# LED_Controller_4Channels.net
KiCad netlist of a schematic drawn in Altium Designer
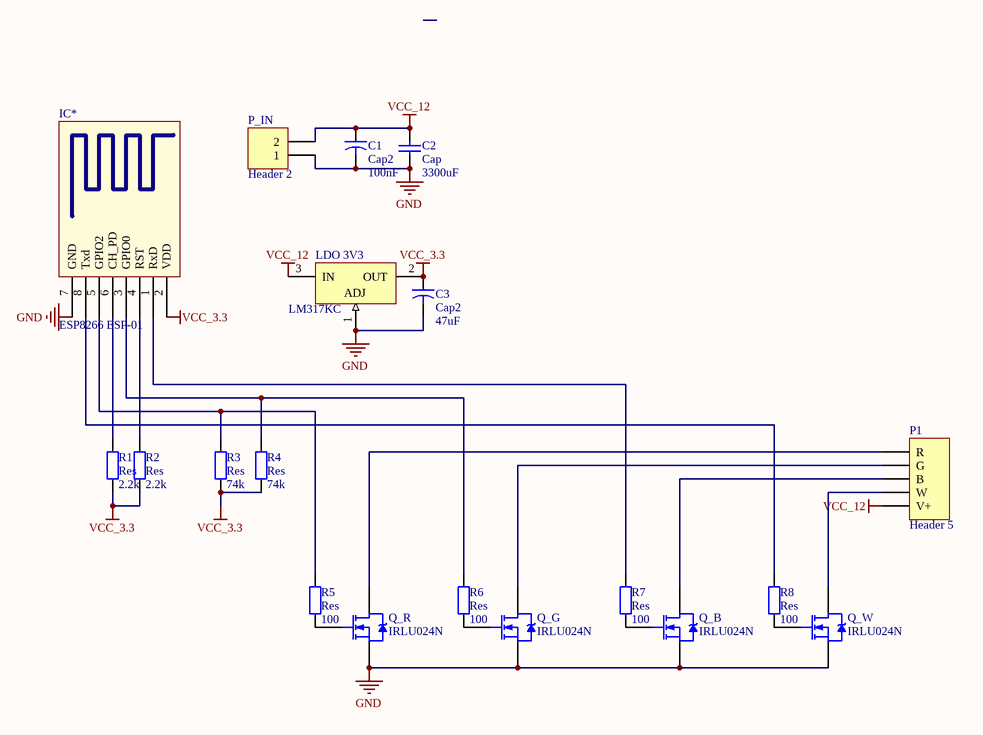
[diagram p0: LED_Controller_4Channels.SchDoc]

(export (version "E")
  (design (tool "Eeschema 10.0.6"))
  (components
    (comp (ref "C1")
      (value "Cap2")
      (footprint "CAPR5-4X5")
      (description "Capacitor")
      (fields (field (name "ALTIUM_VALUE") "100nF") (field (name "PUBLISHER") "Altium Limited"))
      (libsource (lib "Miscellaneous Devices") (part "Cap2"))
    )
    (comp (ref "C2")
      (value "Cap")
      (footprint "RAD-0.3")
      (description "Capacitor")
      (fields (field (name "ALTIUM_VALUE") "3300uF") (field (name "PUBLISHER") "Altium Limited"))
      (libsource (lib "Miscellaneous Devices") (part "Cap"))
    )
    (comp (ref "C3")
      (value "Cap2")
      (footprint "CAPR5-4X5")
      (description "Capacitor")
      (fields (field (name "ALTIUM_VALUE") "47uF") (field (name "PUBLISHER") "Altium Limited"))
      (libsource (lib "Miscellaneous Devices") (part "Cap2"))
    )
    (comp (ref "IC*")
      (value "ESP8266 ESP-01")
      (footprint "ESP8266:ESP8266 ESP-01")
      (libsource (lib "ESP8266") (part "ESP8266 ESP-01"))
    )
    (comp (ref "LDO 3V3")
      (value "LM317KC")
      (footprint "KC03")
      (description "3-Terminal Adjustable Regulator")
      (fields (field (name "PUBLISHER") "Altium Limited"))
      (libsource (lib "TI Power Mgt Voltage Regulator") (part "LM317KC"))
    )
    (comp (ref "P1")
      (value "Header 5")
      (footprint "HDR1X5")
      (description "Header, 5-Pin")
      (fields (field (name "PUBLISHER") "Altium Limited"))
      (libsource (lib "Miscellaneous Connectors") (part "Header 5"))
    )
    (comp (ref "P_IN")
      (value "Header 2")
      (footprint "HDR1X2")
      (description "Header, 2-Pin")
      (fields (field (name "PUBLISHER") "Altium Limited"))
      (libsource (lib "Miscellaneous Connectors") (part "Header 2"))
    )
    (comp (ref "Q_B")
      (value "IRLU024N")
      (footprint "D-Pack")
      (description "HEXFET Power MOSFET")
      (fields (field (name "PUBLISHER") "Altium Limited"))
      (libsource (lib "cadLib") (part "IRLU024N"))
    )
    (comp (ref "Q_G")
      (value "IRLU024N")
      (footprint "D-Pack")
      (description "HEXFET Power MOSFET")
      (fields (field (name "PUBLISHER") "Altium Limited"))
      (libsource (lib "cadLib") (part "IRLU024N"))
    )
    (comp (ref "Q_R")
      (value "IRLU024N")
      (footprint "D-Pack")
      (description "HEXFET Power MOSFET")
      (fields (field (name "PUBLISHER") "Altium Limited"))
      (libsource (lib "cadLib") (part "IRLU024N"))
    )
    (comp (ref "Q_W")
      (value "IRLU024N")
      (footprint "D-Pack")
      (description "HEXFET Power MOSFET")
      (fields (field (name "PUBLISHER") "Altium Limited"))
      (libsource (lib "cadLib") (part "IRLU024N"))
    )
    (comp (ref "R1")
      (value "Res")
      (footprint "0805")
      (description "Resistor")
      (fields (field (name "ALTIUM_VALUE") "2.2k") (field (name "PUBLISHER") "Altium Limited"))
      (libsource (lib "") (part "Res_1"))
    )
    (comp (ref "R2")
      (value "Res")
      (footprint "0805")
      (description "Resistor")
      (fields (field (name "ALTIUM_VALUE") "2.2k") (field (name "PUBLISHER") "Altium Limited"))
      (libsource (lib "") (part "Res_1"))
    )
    (comp (ref "R3")
      (value "Res")
      (footprint "0805")
      (description "Resistor")
      (fields (field (name "ALTIUM_VALUE") "74k") (field (name "PUBLISHER") "Altium Limited"))
      (libsource (lib "MiscDevices") (part "Res"))
    )
    (comp (ref "R4")
      (value "Res")
      (footprint "0805")
      (description "Resistor")
      (fields (field (name "ALTIUM_VALUE") "74k") (field (name "PUBLISHER") "Altium Limited"))
      (libsource (lib "MiscDevices") (part "Res"))
    )
    (comp (ref "R5")
      (value "Res")
      (footprint "0805")
      (description "Resistor")
      (fields (field (name "ALTIUM_VALUE") "100") (field (name "PUBLISHER") "Altium Limited"))
      (libsource (lib "") (part "Res_1"))
    )
    (comp (ref "R6")
      (value "Res")
      (footprint "0805")
      (description "Resistor")
      (fields (field (name "ALTIUM_VALUE") "100") (field (name "PUBLISHER") "Altium Limited"))
      (libsource (lib "") (part "Res_1"))
    )
    (comp (ref "R7")
      (value "Res")
      (footprint "0805")
      (description "Resistor")
      (fields (field (name "ALTIUM_VALUE") "100") (field (name "PUBLISHER") "Altium Limited"))
      (libsource (lib "") (part "Res_1"))
    )
    (comp (ref "R8")
      (value "Res")
      (footprint "0805")
      (description "Resistor")
      (fields (field (name "ALTIUM_VALUE") "100") (field (name "PUBLISHER") "Altium Limited"))
      (libsource (lib "") (part "Res_1"))
    )
  )
  (nets
    (net (code "1") (name "GND") (class "Default")
      (node (ref "C1") (pin "2") (pinfunction "2_2") (pintype "passive"))
      (node (ref "C2") (pin "1") (pinfunction "1_1") (pintype "passive"))
      (node (ref "C3") (pin "2") (pinfunction "2_2") (pintype "passive"))
      (node (ref "IC*") (pin "7") (pinfunction "GND_7") (pintype "passive"))
      (node (ref "LDO 3V3") (pin "1") (pinfunction "ADJ_1") (pintype "input"))
      (node (ref "P_IN") (pin "1") (pinfunction "1_1") (pintype "passive"))
      (node (ref "Q_B") (pin "3") (pinfunction "S_3") (pintype "passive"))
      (node (ref "Q_G") (pin "3") (pinfunction "S_3") (pintype "passive"))
      (node (ref "Q_R") (pin "3") (pinfunction "S_3") (pintype "passive"))
      (node (ref "Q_W") (pin "3") (pinfunction "S_3") (pintype "passive"))
    )
    (net (code "2") (name "Net-(IC*-CH_PD)") (class "Default")
      (node (ref "IC*") (pin "6") (pinfunction "CH_PD_6") (pintype "passive"))
      (node (ref "R1") (pin "2") (pinfunction "2_2") (pintype "passive"))
    )
    (net (code "3") (name "Net-(IC*-GPIO0)") (class "Default")
      (node (ref "IC*") (pin "3") (pinfunction "GPIO0_3") (pintype "passive"))
      (node (ref "R4") (pin "1") (pinfunction "1_1") (pintype "passive"))
      (node (ref "R6") (pin "2") (pinfunction "2_2") (pintype "passive"))
    )
    (net (code "4") (name "Net-(IC*-GPIO2)") (class "Default")
      (node (ref "IC*") (pin "5") (pinfunction "GPIO2_5") (pintype "passive"))
      (node (ref "R3") (pin "1") (pinfunction "1_1") (pintype "passive"))
      (node (ref "R5") (pin "2") (pinfunction "2_2") (pintype "passive"))
    )
    (net (code "5") (name "Net-(IC*-RST)") (class "Default")
      (node (ref "IC*") (pin "4") (pinfunction "RST_4") (pintype "passive"))
      (node (ref "R2") (pin "2") (pinfunction "2_2") (pintype "passive"))
    )
    (net (code "6") (name "Net-(IC*-RxD)") (class "Default")
      (node (ref "IC*") (pin "1") (pinfunction "RxD_1") (pintype "passive"))
      (node (ref "R7") (pin "2") (pinfunction "2_2") (pintype "passive"))
    )
    (net (code "7") (name "Net-(IC*-Txd)") (class "Default")
      (node (ref "IC*") (pin "8") (pinfunction "Txd_8") (pintype "passive"))
      (node (ref "R8") (pin "2") (pinfunction "2_2") (pintype "passive"))
    )
    (net (code "8") (name "Net-(P1-B)") (class "Default")
      (node (ref "P1") (pin "3") (pinfunction "B_3") (pintype "passive"))
      (node (ref "Q_B") (pin "2") (pinfunction "D_2") (pintype "passive"))
    )
    (net (code "9") (name "Net-(P1-G)") (class "Default")
      (node (ref "P1") (pin "2") (pinfunction "G_2") (pintype "passive"))
      (node (ref "Q_G") (pin "2") (pinfunction "D_2") (pintype "passive"))
    )
    (net (code "10") (name "Net-(P1-R)") (class "Default")
      (node (ref "P1") (pin "1") (pinfunction "R_1") (pintype "passive"))
      (node (ref "Q_R") (pin "2") (pinfunction "D_2") (pintype "passive"))
    )
    (net (code "11") (name "Net-(P1-W)") (class "Default")
      (node (ref "P1") (pin "4") (pinfunction "W_4") (pintype "passive"))
      (node (ref "Q_W") (pin "2") (pinfunction "D_2") (pintype "passive"))
    )
    (net (code "12") (name "Net-(Q_B-G)") (class "Default")
      (node (ref "Q_B") (pin "1") (pinfunction "G_1") (pintype "passive"))
      (node (ref "R7") (pin "1") (pinfunction "1_1") (pintype "passive"))
    )
    (net (code "13") (name "Net-(Q_G-G)") (class "Default")
      (node (ref "Q_G") (pin "1") (pinfunction "G_1") (pintype "passive"))
      (node (ref "R6") (pin "1") (pinfunction "1_1") (pintype "passive"))
    )
    (net (code "14") (name "Net-(Q_R-G)") (class "Default")
      (node (ref "Q_R") (pin "1") (pinfunction "G_1") (pintype "passive"))
      (node (ref "R5") (pin "1") (pinfunction "1_1") (pintype "passive"))
    )
    (net (code "15") (name "Net-(Q_W-G)") (class "Default")
      (node (ref "Q_W") (pin "1") (pinfunction "G_1") (pintype "passive"))
      (node (ref "R8") (pin "1") (pinfunction "1_1") (pintype "passive"))
    )
    (net (code "16") (name "VCC_3.3") (class "Default")
      (node (ref "C3") (pin "1") (pinfunction "1_1") (pintype "passive"))
      (node (ref "IC*") (pin "2") (pinfunction "VDD_2") (pintype "passive"))
      (node (ref "LDO 3V3") (pin "2") (pinfunction "OUT_2") (pintype "power_in"))
      (node (ref "R1") (pin "1") (pinfunction "1_1") (pintype "passive"))
      (node (ref "R2") (pin "1") (pinfunction "1_1") (pintype "passive"))
      (node (ref "R3") (pin "2") (pinfunction "2_2") (pintype "passive"))
      (node (ref "R4") (pin "2") (pinfunction "2_2") (pintype "passive"))
    )
    (net (code "17") (name "VCC_12") (class "Default")
      (node (ref "C1") (pin "1") (pinfunction "1_1") (pintype "passive"))
      (node (ref "C2") (pin "2") (pinfunction "2_2") (pintype "passive"))
      (node (ref "LDO 3V3") (pin "3") (pinfunction "IN_3") (pintype "power_in"))
      (node (ref "P1") (pin "5") (pinfunction "V+_5") (pintype "passive"))
      (node (ref "P_IN") (pin "2") (pinfunction "2_2") (pintype "passive"))
    )
  )
)
